# 435MHz_LNA.net
KiCad netlist of a schematic drawn in Altium Designer
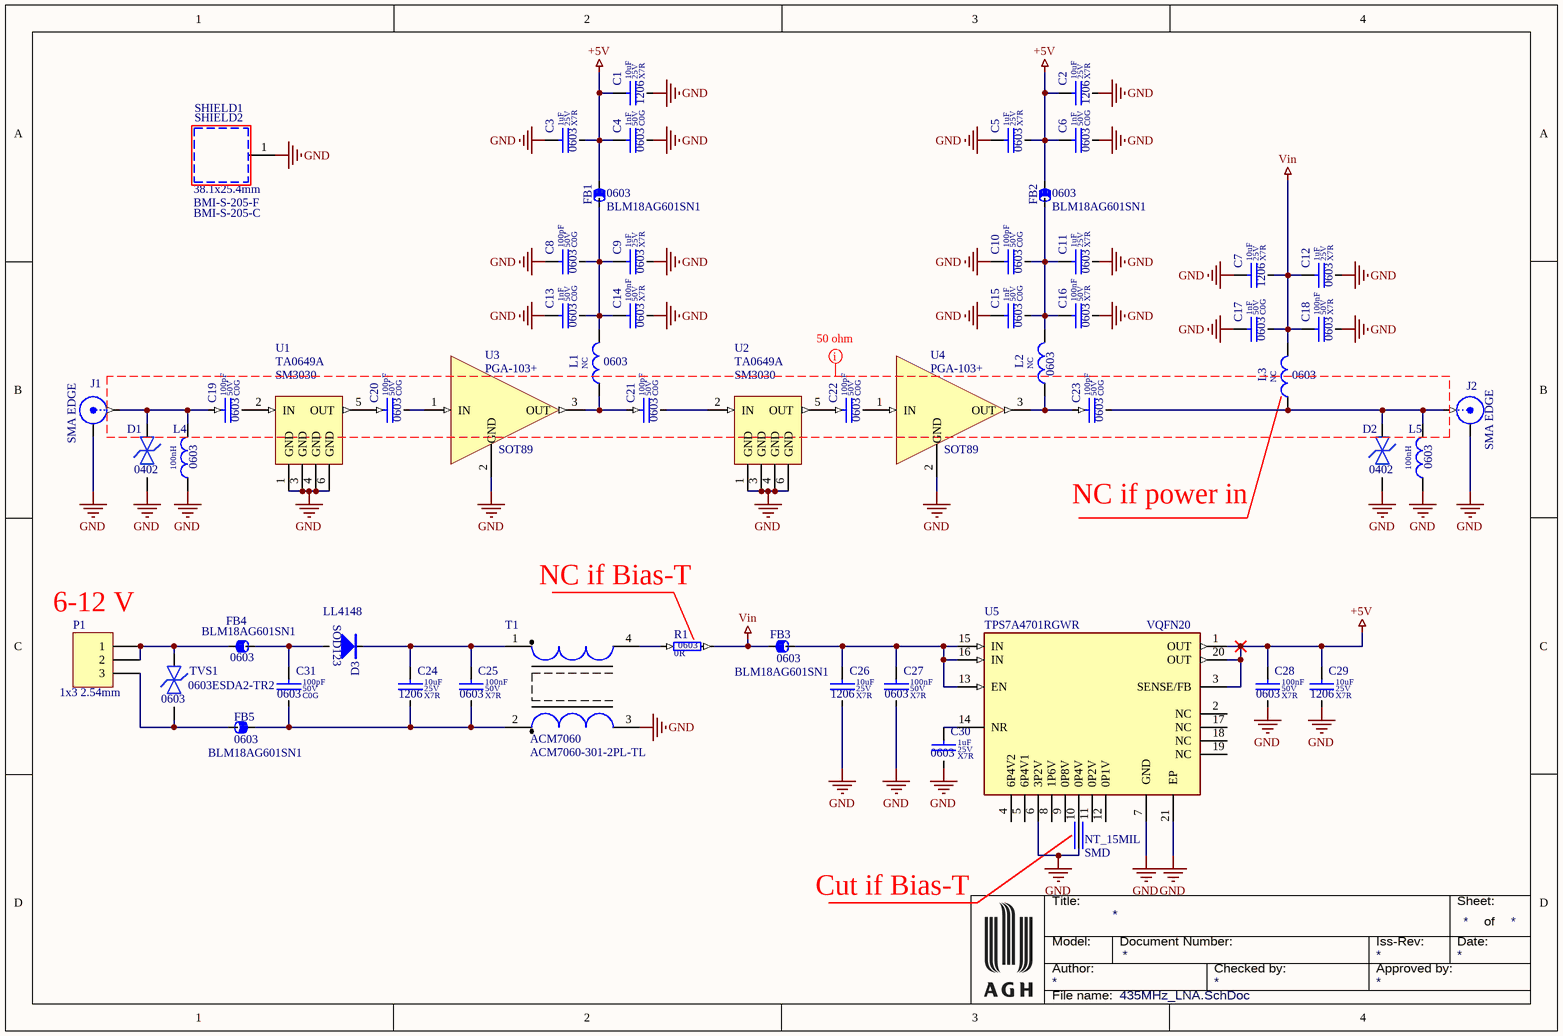
[diagram p0: 435MHz_LNA.SchDoc]

(export (version "E")
  (design (tool "Eeschema 10.0.6"))
  (components
    (comp (ref "C1")
      (value "10uF")
      (footprint "C_1206_3216")
      (description "Capacitor")
      (fields
        (field (name "DIELECTRIC") "X7R")
        (field (name "VOLTAGE") "25V")
        (field (name "SCH_FOOTPRINT") "1206")
        (field (name "PART NUMBER") "C_10uF_25V_X7R_1206_10")
        (field (name "MANUFACTURER") "Samsung Electro-Mechanics")
      )
      (libsource (lib "Library") (part "C"))
    )
    (comp (ref "C2")
      (value "10uF")
      (footprint "C_1206_3216")
      (description "Capacitor")
      (fields
        (field (name "DIELECTRIC") "X7R")
        (field (name "VOLTAGE") "25V")
        (field (name "SCH_FOOTPRINT") "1206")
        (field (name "PART NUMBER") "C_10uF_25V_X7R_1206_10")
        (field (name "MANUFACTURER") "Samsung Electro-Mechanics")
      )
      (libsource (lib "Library") (part "C"))
    )
    (comp (ref "C3")
      (value "1uF")
      (footprint "C_0603_1608")
      (description "Capacitor")
      (fields
        (field (name "DIELECTRIC") "X7R")
        (field (name "VOLTAGE") "25V")
        (field (name "SCH_FOOTPRINT") "0603")
        (field (name "PART NUMBER") "C_1uF_25V_X7R_0603_10")
        (field (name "MANUFACTURER") "Samsung")
      )
      (libsource (lib "Library") (part "C"))
    )
    (comp (ref "C4")
      (value "1nF")
      (footprint "C_0603_1608")
      (description "Capacitor")
      (fields
        (field (name "DIELECTRIC") "C0G")
        (field (name "VOLTAGE") "50V")
        (field (name "SCH_FOOTPRINT") "0603")
        (field (name "PART NUMBER") "C_1nF_50V_C0G_0603_5")
        (field (name "MANUFACTURER") "Samsung")
      )
      (libsource (lib "Library") (part "C"))
    )
    (comp (ref "C5")
      (value "1uF")
      (footprint "C_0603_1608")
      (description "Capacitor")
      (fields
        (field (name "DIELECTRIC") "X7R")
        (field (name "VOLTAGE") "25V")
        (field (name "SCH_FOOTPRINT") "0603")
        (field (name "PART NUMBER") "C_1uF_25V_X7R_0603_10")
        (field (name "MANUFACTURER") "Samsung")
      )
      (libsource (lib "Library") (part "C"))
    )
    (comp (ref "C6")
      (value "1nF")
      (footprint "C_0603_1608")
      (description "Capacitor")
      (fields
        (field (name "DIELECTRIC") "C0G")
        (field (name "VOLTAGE") "50V")
        (field (name "SCH_FOOTPRINT") "0603")
        (field (name "PART NUMBER") "C_1nF_50V_C0G_0603_5")
        (field (name "MANUFACTURER") "Samsung")
      )
      (libsource (lib "Library") (part "C"))
    )
    (comp (ref "C7")
      (value "10uF")
      (footprint "C_1206_3216")
      (description "Capacitor")
      (fields
        (field (name "DIELECTRIC") "X7R")
        (field (name "VOLTAGE") "25V")
        (field (name "SCH_FOOTPRINT") "1206")
        (field (name "PART NUMBER") "C_10uF_25V_X7R_1206_10")
        (field (name "MANUFACTURER") "Samsung Electro-Mechanics")
      )
      (libsource (lib "Library") (part "C"))
    )
    (comp (ref "C8")
      (value "100pF")
      (footprint "C_0603_1608")
      (description "Capacitor")
      (fields
        (field (name "DIELECTRIC") "C0G")
        (field (name "VOLTAGE") "50V")
        (field (name "SCH_FOOTPRINT") "0603")
        (field (name "PART NUMBER") "C_100pF_50V_C0G_0603_5")
        (field (name "MANUFACTURER") "AVX")
      )
      (libsource (lib "Library") (part "C"))
    )
    (comp (ref "C9")
      (value "1uF")
      (footprint "C_0603_1608")
      (description "Capacitor")
      (fields
        (field (name "DIELECTRIC") "X7R")
        (field (name "VOLTAGE") "25V")
        (field (name "SCH_FOOTPRINT") "0603")
        (field (name "PART NUMBER") "C_1uF_25V_X7R_0603_10")
        (field (name "MANUFACTURER") "Samsung")
      )
      (libsource (lib "Library") (part "C"))
    )
    (comp (ref "C10")
      (value "100pF")
      (footprint "C_0603_1608")
      (description "Capacitor")
      (fields
        (field (name "DIELECTRIC") "C0G")
        (field (name "VOLTAGE") "50V")
        (field (name "SCH_FOOTPRINT") "0603")
        (field (name "PART NUMBER") "C_100pF_50V_C0G_0603_5")
        (field (name "MANUFACTURER") "AVX")
      )
      (libsource (lib "Library") (part "C"))
    )
    (comp (ref "C11")
      (value "1uF")
      (footprint "C_0603_1608")
      (description "Capacitor")
      (fields
        (field (name "DIELECTRIC") "X7R")
        (field (name "VOLTAGE") "25V")
        (field (name "SCH_FOOTPRINT") "0603")
        (field (name "PART NUMBER") "C_1uF_25V_X7R_0603_10")
        (field (name "MANUFACTURER") "Samsung")
      )
      (libsource (lib "Library") (part "C"))
    )
    (comp (ref "C12")
      (value "1uF")
      (footprint "C_0603_1608")
      (description "Capacitor")
      (fields
        (field (name "DIELECTRIC") "X7R")
        (field (name "VOLTAGE") "25V")
        (field (name "SCH_FOOTPRINT") "0603")
        (field (name "PART NUMBER") "C_1uF_25V_X7R_0603_10")
        (field (name "MANUFACTURER") "Samsung")
      )
      (libsource (lib "Library") (part "C"))
    )
    (comp (ref "C13")
      (value "1nF")
      (footprint "C_0603_1608")
      (description "Capacitor")
      (fields
        (field (name "DIELECTRIC") "C0G")
        (field (name "VOLTAGE") "50V")
        (field (name "SCH_FOOTPRINT") "0603")
        (field (name "PART NUMBER") "C_1nF_50V_C0G_0603_5")
        (field (name "MANUFACTURER") "Samsung")
      )
      (libsource (lib "Library") (part "C"))
    )
    (comp (ref "C14")
      (value "100nF")
      (footprint "C_0603_1608")
      (description "Capacitor")
      (fields
        (field (name "DIELECTRIC") "X7R")
        (field (name "VOLTAGE") "50V")
        (field (name "SCH_FOOTPRINT") "0603")
        (field (name "PART NUMBER") "C_100nF_50V_X7R_0603_5")
        (field (name "MANUFACTURER") "Samsung")
      )
      (libsource (lib "Library") (part "C"))
    )
    (comp (ref "C15")
      (value "1nF")
      (footprint "C_0603_1608")
      (description "Capacitor")
      (fields
        (field (name "DIELECTRIC") "C0G")
        (field (name "VOLTAGE") "50V")
        (field (name "SCH_FOOTPRINT") "0603")
        (field (name "PART NUMBER") "C_1nF_50V_C0G_0603_5")
        (field (name "MANUFACTURER") "Samsung")
      )
      (libsource (lib "Library") (part "C"))
    )
    (comp (ref "C16")
      (value "100nF")
      (footprint "C_0603_1608")
      (description "Capacitor")
      (fields
        (field (name "DIELECTRIC") "X7R")
        (field (name "VOLTAGE") "50V")
        (field (name "SCH_FOOTPRINT") "0603")
        (field (name "PART NUMBER") "C_100nF_50V_X7R_0603_5")
        (field (name "MANUFACTURER") "Samsung")
      )
      (libsource (lib "Library") (part "C"))
    )
    (comp (ref "C17")
      (value "1nF")
      (footprint "C_0603_1608")
      (description "Capacitor")
      (fields
        (field (name "DIELECTRIC") "C0G")
        (field (name "VOLTAGE") "50V")
        (field (name "SCH_FOOTPRINT") "0603")
        (field (name "PART NUMBER") "C_1nF_50V_C0G_0603_5")
        (field (name "MANUFACTURER") "Samsung")
      )
      (libsource (lib "Library") (part "C"))
    )
    (comp (ref "C18")
      (value "100nF")
      (footprint "C_0603_1608")
      (description "Capacitor")
      (fields
        (field (name "DIELECTRIC") "X7R")
        (field (name "VOLTAGE") "50V")
        (field (name "SCH_FOOTPRINT") "0603")
        (field (name "PART NUMBER") "C_100nF_50V_X7R_0603_5")
        (field (name "MANUFACTURER") "Samsung")
      )
      (libsource (lib "Library") (part "C"))
    )
    (comp (ref "C19")
      (value "100pF")
      (footprint "C_0603_1608")
      (description "Capacitor")
      (fields
        (field (name "DIELECTRIC") "C0G")
        (field (name "VOLTAGE") "50V")
        (field (name "SCH_FOOTPRINT") "0603")
        (field (name "PART NUMBER") "C_100pF_50V_C0G_0603_5")
        (field (name "MANUFACTURER") "AVX")
      )
      (libsource (lib "") (part "C_1"))
    )
    (comp (ref "C20")
      (value "100pF")
      (footprint "C_0603_1608")
      (description "Capacitor")
      (fields
        (field (name "DIELECTRIC") "C0G")
        (field (name "VOLTAGE") "50V")
        (field (name "SCH_FOOTPRINT") "0603")
        (field (name "PART NUMBER") "C_100pF_50V_C0G_0603_5")
        (field (name "MANUFACTURER") "AVX")
      )
      (libsource (lib "") (part "C_1"))
    )
    (comp (ref "C21")
      (value "100pF")
      (footprint "C_0603_1608")
      (description "Capacitor")
      (fields
        (field (name "DIELECTRIC") "C0G")
        (field (name "VOLTAGE") "50V")
        (field (name "SCH_FOOTPRINT") "0603")
        (field (name "PART NUMBER") "C_100pF_50V_C0G_0603_5")
        (field (name "MANUFACTURER") "AVX")
      )
      (libsource (lib "") (part "C_1"))
    )
    (comp (ref "C22")
      (value "100pF")
      (footprint "C_0603_1608")
      (description "Capacitor")
      (fields
        (field (name "DIELECTRIC") "C0G")
        (field (name "VOLTAGE") "50V")
        (field (name "SCH_FOOTPRINT") "0603")
        (field (name "PART NUMBER") "C_100pF_50V_C0G_0603_5")
        (field (name "MANUFACTURER") "AVX")
      )
      (libsource (lib "") (part "C_1"))
    )
    (comp (ref "C23")
      (value "100pF")
      (footprint "C_0603_1608")
      (description "Capacitor")
      (fields
        (field (name "DIELECTRIC") "C0G")
        (field (name "VOLTAGE") "50V")
        (field (name "SCH_FOOTPRINT") "0603")
        (field (name "PART NUMBER") "C_100pF_50V_C0G_0603_5")
        (field (name "MANUFACTURER") "AVX")
      )
      (libsource (lib "") (part "C_1"))
    )
    (comp (ref "C24")
      (value "10uF")
      (footprint "C_1206_3216")
      (description "Capacitor")
      (fields
        (field (name "DIELECTRIC") "X7R")
        (field (name "VOLTAGE") "25V")
        (field (name "SCH_FOOTPRINT") "1206")
        (field (name "PART NUMBER") "C_10uF_25V_X7R_1206_10")
        (field (name "MANUFACTURER") "Samsung Electro-Mechanics")
      )
      (libsource (lib "Library") (part "C"))
    )
    (comp (ref "C25")
      (value "100nF")
      (footprint "C_0603_1608")
      (description "Capacitor")
      (fields
        (field (name "DIELECTRIC") "X7R")
        (field (name "VOLTAGE") "50V")
        (field (name "SCH_FOOTPRINT") "0603")
        (field (name "PART NUMBER") "C_100nF_50V_X7R_0603_5")
        (field (name "MANUFACTURER") "Samsung")
      )
      (libsource (lib "Library") (part "C"))
    )
    (comp (ref "C26")
      (value "10uF")
      (footprint "C_1206_3216")
      (description "Capacitor")
      (fields
        (field (name "DIELECTRIC") "X7R")
        (field (name "VOLTAGE") "25V")
        (field (name "SCH_FOOTPRINT") "1206")
        (field (name "PART NUMBER") "C_10uF_25V_X7R_1206_10")
        (field (name "MANUFACTURER") "Samsung Electro-Mechanics")
      )
      (libsource (lib "Library") (part "C"))
    )
    (comp (ref "C27")
      (value "100nF")
      (footprint "C_0603_1608")
      (description "Capacitor")
      (fields
        (field (name "DIELECTRIC") "X7R")
        (field (name "VOLTAGE") "50V")
        (field (name "SCH_FOOTPRINT") "0603")
        (field (name "PART NUMBER") "C_100nF_50V_X7R_0603_5")
        (field (name "MANUFACTURER") "Samsung")
      )
      (libsource (lib "Library") (part "C"))
    )
    (comp (ref "C28")
      (value "100nF")
      (footprint "C_0603_1608")
      (description "Capacitor")
      (fields
        (field (name "DIELECTRIC") "X7R")
        (field (name "VOLTAGE") "50V")
        (field (name "SCH_FOOTPRINT") "0603")
        (field (name "PART NUMBER") "C_100nF_50V_X7R_0603_5")
        (field (name "MANUFACTURER") "Samsung")
      )
      (libsource (lib "Library") (part "C"))
    )
    (comp (ref "C29")
      (value "10uF")
      (footprint "C_1206_3216")
      (description "Capacitor")
      (fields
        (field (name "DIELECTRIC") "X7R")
        (field (name "VOLTAGE") "25V")
        (field (name "SCH_FOOTPRINT") "1206")
        (field (name "PART NUMBER") "C_10uF_25V_X7R_1206_10")
        (field (name "MANUFACTURER") "Samsung Electro-Mechanics")
      )
      (libsource (lib "Library") (part "C"))
    )
    (comp (ref "C30")
      (value "1uF")
      (footprint "C_0603_1608")
      (description "Capacitor")
      (fields
        (field (name "DIELECTRIC") "X7R")
        (field (name "VOLTAGE") "25V")
        (field (name "SCH_FOOTPRINT") "0603")
        (field (name "PART NUMBER") "C_1uF_25V_X7R_0603_10")
        (field (name "MANUFACTURER") "Samsung")
      )
      (libsource (lib "Library") (part "C"))
    )
    (comp (ref "C31")
      (value "100pF")
      (footprint "C_0603_1608")
      (description "Capacitor")
      (fields
        (field (name "DIELECTRIC") "C0G")
        (field (name "VOLTAGE") "50V")
        (field (name "SCH_FOOTPRINT") "0603")
        (field (name "PART NUMBER") "C_100pF_50V_C0G_0603_5")
        (field (name "MANUFACTURER") "AVX")
      )
      (libsource (lib "Library") (part "C"))
    )
    (comp (ref "D1")
      (value "ESD Suppressors / TVS Diodes")
      (footprint "D_BI_0402_1005")
      (fields
        (field (name "SCH_FOOTPRINT") "0402")
        (field (name "PART NUMBER") "TVS_PS04LTVA1")
        (field (name "VOLTAGE") "12V")
        (field (name "MANUFACTURER") "Bussmann")
      )
      (libsource (lib "Library") (part "TVS_BI"))
    )
    (comp (ref "D2")
      (value "ESD Suppressors / TVS Diodes")
      (footprint "D_BI_0402_1005")
      (fields
        (field (name "SCH_FOOTPRINT") "0402")
        (field (name "PART NUMBER") "TVS_PS04LTVA1")
        (field (name "VOLTAGE") "12V")
        (field (name "MANUFACTURER") "Bussmann")
      )
      (libsource (lib "Library") (part "TVS_BI"))
    )
    (comp (ref "D3")
      (value "LL4148")
      (footprint "SOD123")
      (fields
        (field (name "PART NUMBER") "D_1N4148W_0A15_75V_SOD123")
        (field (name "VOLTAGE") "75V")
        (field (name "MANUFACTURER") "Fairchild Semiconductor")
      )
      (libsource (lib "Library") (part "D"))
    )
    (comp (ref "FB1")
      (value "BLM18AG601SN1")
      (footprint "FB_0603_1608")
      (description "Ferrite Bead")
      (fields
        (field (name "PART NUMBER") "FB_BLM18AG601SN1")
        (field (name "SCH_FOOTPRINT") "0603")
        (field (name "MANUFACTURER") "Murata")
      )
      (libsource (lib "") (part "FB_2"))
    )
    (comp (ref "FB2")
      (value "BLM18AG601SN1")
      (footprint "FB_0603_1608")
      (description "Ferrite Bead")
      (fields
        (field (name "PART NUMBER") "FB_BLM18AG601SN1")
        (field (name "SCH_FOOTPRINT") "0603")
        (field (name "MANUFACTURER") "Murata")
      )
      (libsource (lib "") (part "FB_2"))
    )
    (comp (ref "FB3")
      (value "BLM18AG601SN1")
      (footprint "FB_0603_1608")
      (description "Ferrite Bead")
      (fields
        (field (name "PART NUMBER") "FB_BLM18AG601SN1")
        (field (name "SCH_FOOTPRINT") "0603")
        (field (name "MANUFACTURER") "Murata")
      )
      (libsource (lib "") (part "FB_1"))
    )
    (comp (ref "FB4")
      (value "BLM18AG601SN1")
      (footprint "FB_0603_1608")
      (description "Ferrite Bead")
      (fields
        (field (name "PART NUMBER") "FB_BLM18AG601SN1")
        (field (name "SCH_FOOTPRINT") "0603")
        (field (name "MANUFACTURER") "Murata")
      )
      (libsource (lib "") (part "FB_1"))
    )
    (comp (ref "FB5")
      (value "BLM18AG601SN1")
      (footprint "FB_0603_1608")
      (description "Ferrite Bead")
      (fields
        (field (name "PART NUMBER") "FB_BLM18AG601SN1")
        (field (name "SCH_FOOTPRINT") "0603")
        (field (name "MANUFACTURER") "Murata")
      )
      (libsource (lib "Library") (part "FB"))
    )
    (comp (ref "J1")
      (value "SMA EDGE")
      (footprint "J_SMA_EDGE_6.25")
      (description "SMA connector")
      (fields
        (field (name "PART NUMBER") "J_SMA_EDGE_6.25")
        (field (name "SCH_FOOTPRINT") "SMA EDGE")
        (field (name "MANUFACTURER") "Adam Tech")
      )
      (libsource (lib "Library") (part "J_SMA"))
    )
    (comp (ref "J2")
      (value "SMA EDGE")
      (footprint "J_SMA_EDGE_6.25")
      (description "SMA connector")
      (fields
        (field (name "PART NUMBER") "J_SMA_EDGE_6.25")
        (field (name "SCH_FOOTPRINT") "SMA EDGE")
        (field (name "MANUFACTURER") "Adam Tech")
      )
      (libsource (lib "") (part "J_SMA_1"))
    )
    (comp (ref "L1")
      (value "NC")
      (footprint "L_0603_1608")
      (description "Induction")
      (fields
        (field (name "SCH_FOOTPRINT") "0603")
        (field (name "PART NUMBER") "L_0603")
        (field (name "Comment") "L")
      )
      (libsource (lib "Library") (part "L"))
    )
    (comp (ref "L2")
      (value "NC")
      (footprint "L_0603_1608")
      (description "Induction")
      (fields
        (field (name "SCH_FOOTPRINT") "0603")
        (field (name "PART NUMBER") "L_0603")
        (field (name "Comment") "L")
      )
      (libsource (lib "Library") (part "L"))
    )
    (comp (ref "L3")
      (value "NC")
      (footprint "L_0603_1608")
      (description "Induction")
      (fields
        (field (name "SCH_FOOTPRINT") "0603")
        (field (name "PART NUMBER") "L_0603")
        (field (name "Comment") "L")
      )
      (libsource (lib "Library") (part "L"))
    )
    (comp (ref "L4")
      (value "100nH")
      (footprint "L_0603_1608")
      (description "Induction")
      (fields
        (field (name "SCH_FOOTPRINT") "0603")
        (field (name "PART NUMBER") "L_100NH_0A3_0603")
        (field (name "MANUFACTURER") "Bourns")
      )
      (libsource (lib "Library") (part "L"))
    )
    (comp (ref "L5")
      (value "100nH")
      (footprint "L_0603_1608")
      (description "Induction")
      (fields
        (field (name "SCH_FOOTPRINT") "0603")
        (field (name "PART NUMBER") "L_100NH_0A3_0603")
        (field (name "MANUFACTURER") "Bourns")
      )
      (libsource (lib "Library") (part "L"))
    )
    (comp (ref "NT1")
      (value "NT_15MIL")
      (footprint "NT_15MIL")
      (fields (field (name "SCH_FOOTPRINT") "SMD") (field (name "Comment") "NETTIE 15MIL"))
      (libsource (lib "Library") (part "NET_TIE"))
    )
    (comp (ref "P1")
      (value "Goldpin")
      (footprint "P_HEADER_1x3_2.54")
      (description "Header, 3-Pin")
      (fields
        (field (name "PART NUMBER") "P_HEADER_1x3_2.54")
        (field (name "SCH_FOOTPRINT") "1x3 2.54mm")
        (field (name "MANUFACTURER") "Connfly")
      )
      (libsource (lib "Library") (part "P_HEADER_1x3"))
    )
    (comp (ref "R1")
      (value "0R")
      (footprint "R_0603_1608")
      (fields
        (field (name "SCH_FOOTPRINT") "0603")
        (field (name "PART NUMBER") "R_0R_0603")
        (field (name "MANUFACTURER PART NUMBER") "RC1608J000CS")
        (field (name "Comment") "Resistor")
      )
      (libsource (lib "Library") (part "R"))
    )
    (comp (ref "SHIELD1")
      (value "BMI-S-205-C")
      (footprint "BMI-S-205-C")
      (description "Shield, 1 pad")
      (fields (field (name "PART NUMBER") "SHIELD_BMI-S-205-C") (field (name "MANUFACTURER") "Laird"))
      (libsource (lib "Library") (part "SHIELD_COVER"))
    )
    (comp (ref "SHIELD2")
      (value "BMI-S-205-F")
      (footprint "BMI-S-205-F")
      (description "Shield, 1 pad")
      (fields
        (field (name "PART NUMBER") "SHIELD_BMI-S-205-F")
        (field (name "SCH_FOOTPRINT") "38.1x25.4mm")
        (field (name "MANUFACTURER") "Laird")
      )
      (libsource (lib "Library") (part "SHIELD"))
    )
    (comp (ref "T1")
      (value "ACM7060-301-2PL-TL")
      (footprint "ACM7060")
      (description "TDK ACM7060 common mode filter")
      (fields
        (field (name "SCH_FOOTPRINT") "ACM7060")
        (field (name "VOLTAGE") "80")
        (field (name "MANUFACTURER") "TDK")
      )
      (libsource (lib "Library") (part "LM_ACM7060"))
    )
    (comp (ref "TVS1")
      (value "0603ESDA2-TR2")
      (footprint "R_0603_1608")
      (fields
        (field (name "SCH_FOOTPRINT") "0603")
        (field (name "PART NUMBER") "TVS_0603ESDA2")
        (field (name "VOLTAGE") "14V")
        (field (name "MANUFACTURER") "Bussmann")
      )
      (libsource (lib "Library") (part "TVS_BI"))
    )
    (comp (ref "U1")
      (value "TA0649A")
      (footprint "SAW_DCC6_SM3030-6_3x3")
      (fields
        (field (name "PART NUMBER") "U_TA0649A")
        (field (name "SCH_FOOTPRINT") "SM3030")
        (field (name "MANUFACTURER") "Tai-Saw")
      )
      (libsource (lib "Library") (part "U_SAW6_2_5"))
    )
    (comp (ref "U2")
      (value "TA0649A")
      (footprint "SAW_DCC6_SM3030-6_3x3")
      (fields
        (field (name "PART NUMBER") "U_TA0649A")
        (field (name "SCH_FOOTPRINT") "SM3030")
        (field (name "MANUFACTURER") "Tai-Saw")
      )
      (libsource (lib "Library") (part "U_SAW6_2_5"))
    )
    (comp (ref "U3")
      (value "PGA-103+")
      (footprint "SOT89_TO-243AA_N")
      (fields
        (field (name "PART NUMBER") "U_PGA103+")
        (field (name "SCH_FOOTPRINT") "SOT89")
        (field (name "MANUFACTURER") "Mini-Circuits")
        (field (name "Comment") "PGA103+")
      )
      (libsource (lib "Library") (part "U_PGA103+"))
    )
    (comp (ref "U4")
      (value "PGA-103+")
      (footprint "SOT89_TO-243AA_N")
      (fields
        (field (name "PART NUMBER") "U_PGA103+")
        (field (name "SCH_FOOTPRINT") "SOT89")
        (field (name "MANUFACTURER") "Mini-Circuits")
        (field (name "Comment") "PGA103+")
      )
      (libsource (lib "Library") (part "U_PGA103+"))
    )
    (comp (ref "U5")
      (value "TPS7A4701RGWR")
      (footprint "QFN20_5x5")
      (description "RF LDO Voltage Regulator")
      (fields
        (field (name "SCH_FOOTPRINT") "VQFN20")
        (field (name "PART NUMBER") "VL_TPS7A4701RGWR_ADJ_1A")
        (field (name "VOLTAGE") "ADJ")
      )
      (libsource (lib "Library") (part "VL_TPS7A470X"))
    )
  )
  (nets
    (net (code "1") (name "+5V") (class "Default")
      (node (ref "C1") (pin "1") (pinfunction "1_1") (pintype "passive"))
      (node (ref "C2") (pin "1") (pinfunction "1_1") (pintype "passive"))
      (node (ref "C28") (pin "1") (pinfunction "1_1") (pintype "passive"))
      (node (ref "C29") (pin "1") (pinfunction "1_1") (pintype "passive"))
      (node (ref "C3") (pin "2") (pinfunction "2_2") (pintype "passive"))
      (node (ref "C4") (pin "1") (pinfunction "1_1") (pintype "passive"))
      (node (ref "C5") (pin "2") (pinfunction "2_2") (pintype "passive"))
      (node (ref "C6") (pin "1") (pinfunction "1_1") (pintype "passive"))
      (node (ref "FB1") (pin "1") (pintype "input"))
      (node (ref "FB2") (pin "1") (pintype "input"))
      (node (ref "U5") (pin "1") (pinfunction "OUT_1") (pintype "output"))
      (node (ref "U5") (pin "20") (pinfunction "OUT_20") (pintype "output"))
      (node (ref "U5") (pin "3") (pinfunction "SENSE/FB_3") (pintype "passive"))
    )
    (net (code "2") (name "GND") (class "Default")
      (node (ref "C1") (pin "2") (pinfunction "2_2") (pintype "passive"))
      (node (ref "C10") (pin "1") (pinfunction "1_1") (pintype "passive"))
      (node (ref "C11") (pin "2") (pinfunction "2_2") (pintype "passive"))
      (node (ref "C12") (pin "2") (pinfunction "2_2") (pintype "passive"))
      (node (ref "C13") (pin "1") (pinfunction "1_1") (pintype "passive"))
      (node (ref "C14") (pin "2") (pinfunction "2_2") (pintype "passive"))
      (node (ref "C15") (pin "1") (pinfunction "1_1") (pintype "passive"))
      (node (ref "C16") (pin "2") (pinfunction "2_2") (pintype "passive"))
      (node (ref "C17") (pin "1") (pinfunction "1_1") (pintype "passive"))
      (node (ref "C18") (pin "2") (pinfunction "2_2") (pintype "passive"))
      (node (ref "C2") (pin "2") (pinfunction "2_2") (pintype "passive"))
      (node (ref "C26") (pin "2") (pinfunction "2_2") (pintype "passive"))
      (node (ref "C27") (pin "2") (pinfunction "2_2") (pintype "passive"))
      (node (ref "C28") (pin "2") (pinfunction "2_2") (pintype "passive"))
      (node (ref "C29") (pin "2") (pinfunction "2_2") (pintype "passive"))
      (node (ref "C3") (pin "1") (pinfunction "1_1") (pintype "passive"))
      (node (ref "C30") (pin "2") (pinfunction "2_2") (pintype "passive"))
      (node (ref "C4") (pin "2") (pinfunction "2_2") (pintype "passive"))
      (node (ref "C5") (pin "1") (pinfunction "1_1") (pintype "passive"))
      (node (ref "C6") (pin "2") (pinfunction "2_2") (pintype "passive"))
      (node (ref "C7") (pin "1") (pinfunction "1_1") (pintype "passive"))
      (node (ref "C8") (pin "1") (pinfunction "1_1") (pintype "passive"))
      (node (ref "C9") (pin "2") (pinfunction "2_2") (pintype "passive"))
      (node (ref "D1") (pin "2") (pinfunction "2_2") (pintype "passive"))
      (node (ref "D2") (pin "2") (pinfunction "2_2") (pintype "passive"))
      (node (ref "J1") (pin "2") (pinfunction "Y_2") (pintype "passive"))
      (node (ref "J2") (pin "2") (pinfunction "Y_2") (pintype "passive"))
      (node (ref "L4") (pin "1") (pinfunction "1_1") (pintype "passive"))
      (node (ref "L5") (pin "1") (pinfunction "1_1") (pintype "passive"))
      (node (ref "NT1") (pin "1") (pinfunction "1_1") (pintype "passive"))
      (node (ref "SHIELD2") (pin "1") (pinfunction "shield_1") (pintype "passive"))
      (node (ref "T1") (pin "3") (pinfunction "3_3") (pintype "passive"))
      (node (ref "U1") (pin "1") (pinfunction "GND_1") (pintype "power_in"))
      (node (ref "U1") (pin "3") (pinfunction "GND_3") (pintype "power_in"))
      (node (ref "U1") (pin "4") (pinfunction "GND_4") (pintype "power_in"))
      (node (ref "U1") (pin "6") (pinfunction "GND_6") (pintype "power_in"))
      (node (ref "U2") (pin "1") (pinfunction "GND_1") (pintype "power_in"))
      (node (ref "U2") (pin "3") (pinfunction "GND_3") (pintype "power_in"))
      (node (ref "U2") (pin "4") (pinfunction "GND_4") (pintype "power_in"))
      (node (ref "U2") (pin "6") (pinfunction "GND_6") (pintype "power_in"))
      (node (ref "U3") (pin "2") (pinfunction "GND_2") (pintype "power_in"))
      (node (ref "U4") (pin "2") (pinfunction "GND_2") (pintype "power_in"))
      (node (ref "U5") (pin "21") (pinfunction "EP_21") (pintype "power_in"))
      (node (ref "U5") (pin "6") (pinfunction "3P2V_6") (pintype "passive"))
      (node (ref "U5") (pin "7") (pinfunction "GND_7") (pintype "power_in"))
    )
    (net (code "3") (name "Net-(C10-Pad2)") (class "Default")
      (node (ref "C10") (pin "2") (pinfunction "2_2") (pintype "passive"))
      (node (ref "C11") (pin "1") (pinfunction "1_1") (pintype "passive"))
      (node (ref "C15") (pin "2") (pinfunction "2_2") (pintype "passive"))
      (node (ref "C16") (pin "1") (pinfunction "1_1") (pintype "passive"))
      (node (ref "FB2") (pin "2") (pintype "output"))
      (node (ref "L2") (pin "2") (pinfunction "2_2") (pintype "passive"))
    )
    (net (code "4") (name "Net-(C13-Pad2)") (class "Default")
      (node (ref "C13") (pin "2") (pinfunction "2_2") (pintype "passive"))
      (node (ref "C14") (pin "1") (pinfunction "1_1") (pintype "passive"))
      (node (ref "C8") (pin "2") (pinfunction "2_2") (pintype "passive"))
      (node (ref "C9") (pin "1") (pinfunction "1_1") (pintype "passive"))
      (node (ref "FB1") (pin "2") (pintype "output"))
      (node (ref "L1") (pin "2") (pinfunction "2_2") (pintype "passive"))
    )
    (net (code "5") (name "Net-(C24-Pad1)") (class "Default")
      (node (ref "C24") (pin "1") (pinfunction "1_1") (pintype "passive"))
      (node (ref "C25") (pin "1") (pinfunction "1_1") (pintype "passive"))
      (node (ref "D3") (pin "1") (pintype "passive"))
      (node (ref "T1") (pin "1") (pinfunction "1_1") (pintype "passive"))
    )
    (net (code "6") (name "Net-(C24-Pad2)") (class "Default")
      (node (ref "C24") (pin "2") (pinfunction "2_2") (pintype "passive"))
      (node (ref "C25") (pin "2") (pinfunction "2_2") (pintype "passive"))
      (node (ref "C31") (pin "2") (pinfunction "2_2") (pintype "passive"))
      (node (ref "FB5") (pin "1") (pintype "input"))
      (node (ref "T1") (pin "2") (pinfunction "2_2") (pintype "passive"))
    )
    (net (code "7") (name "Net-(C31-Pad1)") (class "Default")
      (node (ref "C31") (pin "1") (pinfunction "1_1") (pintype "passive"))
      (node (ref "D3") (pin "2") (pintype "passive"))
      (node (ref "FB4") (pin "2") (pintype "output"))
    )
    (net (code "8") (name "Net-(FB4-Pad1)") (class "Default")
      (node (ref "FB4") (pin "1") (pintype "input"))
      (node (ref "P1") (pin "1") (pinfunction "1_1") (pintype "passive"))
      (node (ref "P1") (pin "2") (pinfunction "2_2") (pintype "passive"))
      (node (ref "TVS1") (pin "1") (pinfunction "1_1") (pintype "passive"))
    )
    (net (code "9") (name "Net-(FB5-Pad2)") (class "Default")
      (node (ref "FB5") (pin "2") (pintype "output"))
      (node (ref "P1") (pin "3") (pinfunction "3_3") (pintype "passive"))
      (node (ref "TVS1") (pin "2") (pinfunction "2_2") (pintype "passive"))
    )
    (net (code "10") (name "Net-(J1-X)") (class "Default")
      (node (ref "C19") (pin "1") (pinfunction "1_1") (pintype "input"))
      (node (ref "D1") (pin "1") (pinfunction "1_1") (pintype "passive"))
      (node (ref "J1") (pin "1") (pinfunction "X_1") (pintype "output"))
      (node (ref "L4") (pin "2") (pinfunction "2_2") (pintype "passive"))
    )
    (net (code "11") (name "Net-(J2-X)") (class "Default")
      (node (ref "C23") (pin "2") (pinfunction "2_2") (pintype "output"))
      (node (ref "D2") (pin "1") (pinfunction "1_1") (pintype "passive"))
      (node (ref "J2") (pin "1") (pinfunction "X_1") (pintype "input"))
      (node (ref "L3") (pin "1") (pinfunction "1_1") (pintype "passive"))
      (node (ref "L5") (pin "2") (pinfunction "2_2") (pintype "passive"))
    )
    (net (code "12") (name "Net-(R1-Pad1)") (class "Default")
      (node (ref "R1") (pin "1") (pinfunction "1_1") (pintype "input"))
      (node (ref "T1") (pin "4") (pinfunction "4_4") (pintype "passive"))
    )
    (net (code "13") (name "Net-(U1-IN)") (class "Default")
      (node (ref "C19") (pin "2") (pinfunction "2_2") (pintype "output"))
      (node (ref "U1") (pin "2") (pinfunction "IN_2") (pintype "input"))
    )
    (net (code "14") (name "Net-(U1-OUT)") (class "Default")
      (node (ref "C20") (pin "1") (pinfunction "1_1") (pintype "input"))
      (node (ref "U1") (pin "5") (pinfunction "OUT_5") (pintype "output"))
    )
    (net (code "15") (name "Net-(U2-IN)") (class "Default")
      (node (ref "C21") (pin "2") (pinfunction "2_2") (pintype "output"))
      (node (ref "U2") (pin "2") (pinfunction "IN_2") (pintype "input"))
    )
    (net (code "16") (name "Net-(U2-OUT)") (class "Default")
      (node (ref "C22") (pin "1") (pinfunction "1_1") (pintype "input"))
      (node (ref "U2") (pin "5") (pinfunction "OUT_5") (pintype "output"))
    )
    (net (code "17") (name "Net-(U3-IN)") (class "Default")
      (node (ref "C20") (pin "2") (pinfunction "2_2") (pintype "output"))
      (node (ref "U3") (pin "1") (pinfunction "IN_1") (pintype "input"))
    )
    (net (code "18") (name "Net-(U3-OUT)") (class "Default")
      (node (ref "C21") (pin "1") (pinfunction "1_1") (pintype "input"))
      (node (ref "L1") (pin "1") (pinfunction "1_1") (pintype "passive"))
      (node (ref "U3") (pin "3") (pinfunction "OUT_3") (pintype "output"))
    )
    (net (code "19") (name "Net-(U4-IN)") (class "Default")
      (node (ref "C22") (pin "2") (pinfunction "2_2") (pintype "output"))
      (node (ref "U4") (pin "1") (pinfunction "IN_1") (pintype "input"))
    )
    (net (code "20") (name "Net-(U4-OUT)") (class "Default")
      (node (ref "C23") (pin "1") (pinfunction "1_1") (pintype "input"))
      (node (ref "L2") (pin "1") (pinfunction "1_1") (pintype "passive"))
      (node (ref "U4") (pin "3") (pinfunction "OUT_3") (pintype "output"))
    )
    (net (code "21") (name "Net-(U5-0P4V)") (class "Default")
      (node (ref "NT1") (pin "2") (pinfunction "2_2") (pintype "passive"))
      (node (ref "U5") (pin "10") (pinfunction "0P4V_10") (pintype "passive"))
    )
    (net (code "22") (name "Net-(U5-EN)") (class "Default")
      (node (ref "C26") (pin "1") (pinfunction "1_1") (pintype "passive"))
      (node (ref "C27") (pin "1") (pinfunction "1_1") (pintype "passive"))
      (node (ref "FB3") (pin "2") (pintype "output"))
      (node (ref "U5") (pin "13") (pinfunction "EN_13") (pintype "input"))
      (node (ref "U5") (pin "15") (pinfunction "IN_15") (pintype "input"))
      (node (ref "U5") (pin "16") (pinfunction "IN_16") (pintype "input"))
    )
    (net (code "23") (name "Net-(U5-NR)") (class "Default")
      (node (ref "C30") (pin "1") (pinfunction "1_1") (pintype "passive"))
      (node (ref "U5") (pin "14") (pinfunction "NR_14") (pintype "passive"))
    )
    (net (code "24") (name "Vin") (class "Default")
      (node (ref "C12") (pin "1") (pinfunction "1_1") (pintype "passive"))
      (node (ref "C17") (pin "2") (pinfunction "2_2") (pintype "passive"))
      (node (ref "C18") (pin "1") (pinfunction "1_1") (pintype "passive"))
      (node (ref "C7") (pin "2") (pinfunction "2_2") (pintype "passive"))
      (node (ref "FB3") (pin "1") (pintype "input"))
      (node (ref "L3") (pin "2") (pinfunction "2_2") (pintype "passive"))
      (node (ref "R1") (pin "2") (pinfunction "2_2") (pintype "output"))
    )
    (net (code "25") (name "unconnected-(U5-0P1V-Pad12)") (class "Default")
      (node (ref "U5") (pin "12") (pinfunction "0P1V_12") (pintype "passive"))
    )
    (net (code "26") (name "unconnected-(U5-0P2V-Pad11)") (class "Default")
      (node (ref "U5") (pin "11") (pinfunction "0P2V_11") (pintype "passive"))
    )
    (net (code "27") (name "unconnected-(U5-0P8V-Pad9)") (class "Default")
      (node (ref "U5") (pin "9") (pinfunction "0P8V_9") (pintype "passive"))
    )
    (net (code "28") (name "unconnected-(U5-1P6V-Pad8)") (class "Default")
      (node (ref "U5") (pin "8") (pinfunction "1P6V_8") (pintype "passive"))
    )
    (net (code "29") (name "unconnected-(U5-6P4V1-Pad5)") (class "Default")
      (node (ref "U5") (pin "5") (pinfunction "6P4V1_5") (pintype "passive"))
    )
    (net (code "30") (name "unconnected-(U5-6P4V2-Pad4)") (class "Default")
      (node (ref "U5") (pin "4") (pinfunction "6P4V2_4") (pintype "passive"))
    )
    (net (code "31") (name "unconnected-(U5-NC-Pad2)") (class "Default")
      (node (ref "U5") (pin "2") (pinfunction "NC_2") (pintype "passive"))
    )
    (net (code "32") (name "unconnected-(U5-NC-Pad17)") (class "Default")
      (node (ref "U5") (pin "17") (pinfunction "NC_17") (pintype "passive"))
    )
    (net (code "33") (name "unconnected-(U5-NC-Pad18)") (class "Default")
      (node (ref "U5") (pin "18") (pinfunction "NC_18") (pintype "passive"))
    )
    (net (code "34") (name "unconnected-(U5-NC-Pad19)") (class "Default")
      (node (ref "U5") (pin "19") (pinfunction "NC_19") (pintype "passive"))
    )
  )
)
